# input4.net
KiCad netlist of a schematic drawn in Altium Designer
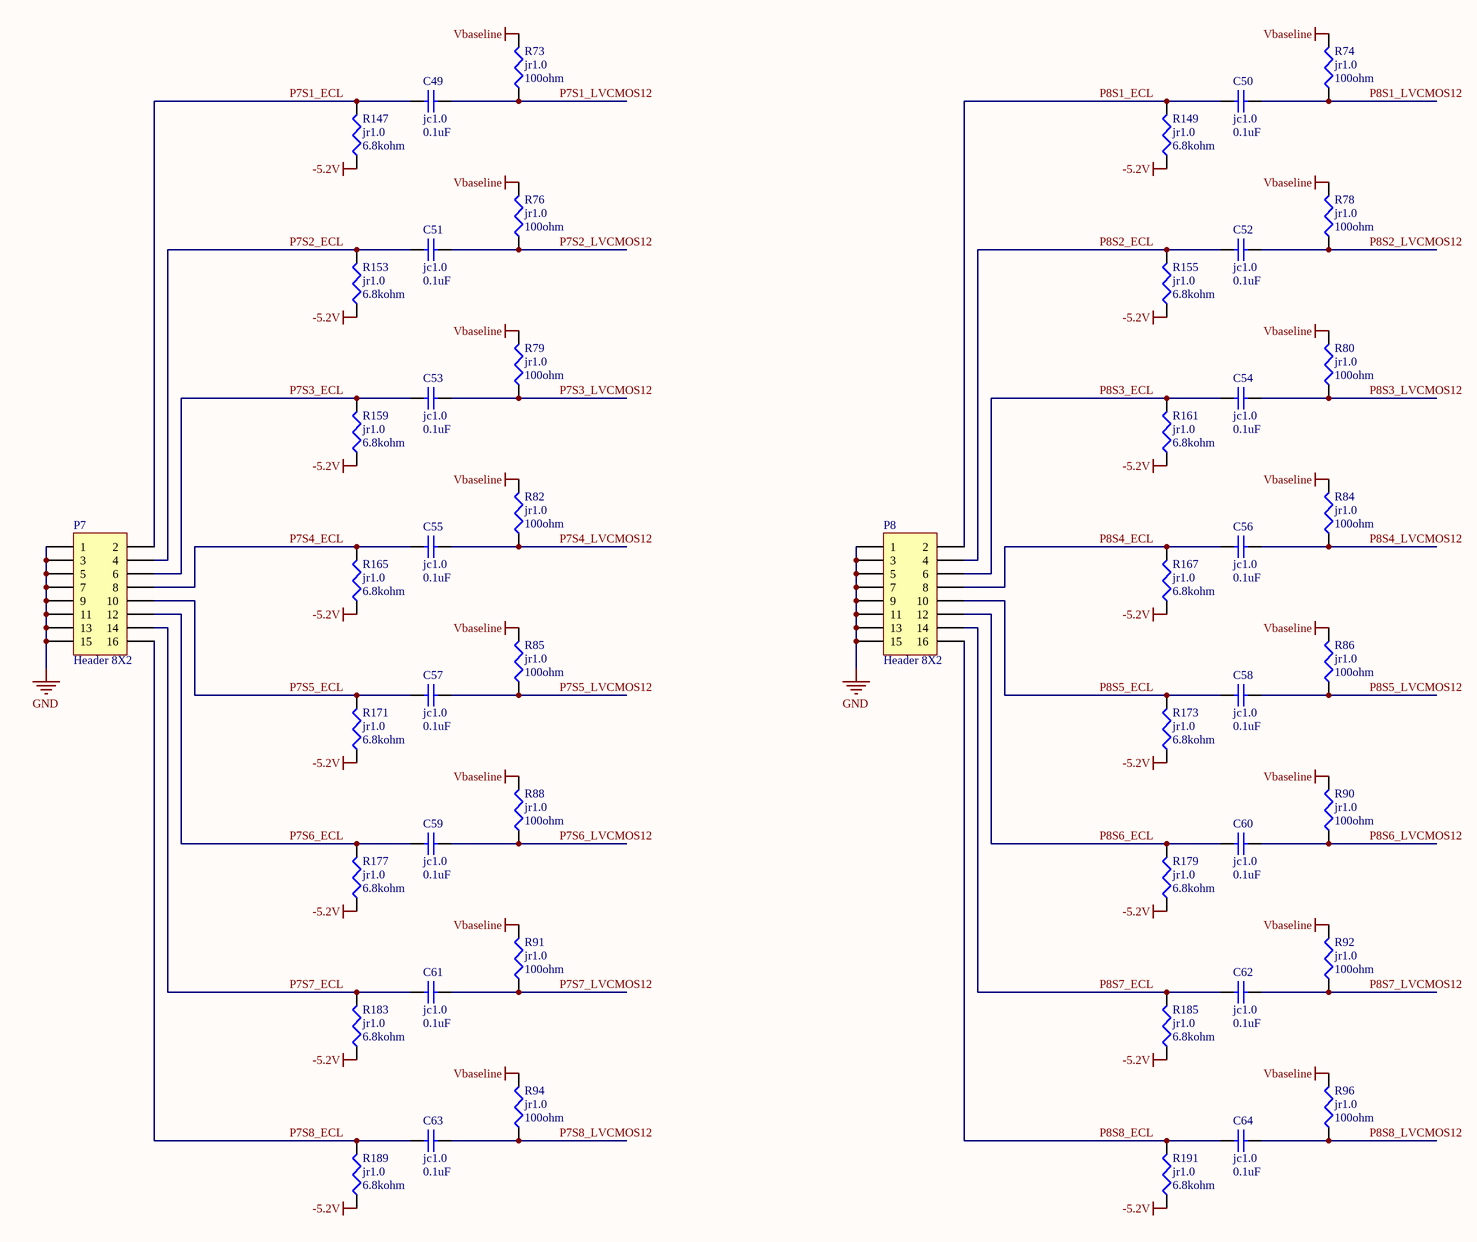
[diagram p0: input4.SchDoc]

(export (version "E")
  (design (tool "Eeschema 10.0.6"))
  (components
    (comp (ref "C49")
      (value "jc1.0")
      (footprint "0402")
      (description "Capacitor")
      (fields (field (name "ALTIUM_VALUE") "0.1uF") (field (name "PUBLISHER") "Altium Limited"))
      (libsource (lib "LIB01DXP2006SchLib") (part "Cap"))
    )
    (comp (ref "C50")
      (value "jc1.0")
      (footprint "0402")
      (description "Capacitor")
      (fields (field (name "ALTIUM_VALUE") "0.1uF") (field (name "PUBLISHER") "Altium Limited"))
      (libsource (lib "LIB01DXP2006SchLib") (part "Cap"))
    )
    (comp (ref "C51")
      (value "jc1.0")
      (footprint "0402")
      (description "Capacitor")
      (fields (field (name "ALTIUM_VALUE") "0.1uF") (field (name "PUBLISHER") "Altium Limited"))
      (libsource (lib "LIB01DXP2006SchLib") (part "Cap"))
    )
    (comp (ref "C52")
      (value "jc1.0")
      (footprint "0402")
      (description "Capacitor")
      (fields (field (name "ALTIUM_VALUE") "0.1uF") (field (name "PUBLISHER") "Altium Limited"))
      (libsource (lib "LIB01DXP2006SchLib") (part "Cap"))
    )
    (comp (ref "C53")
      (value "jc1.0")
      (footprint "0402")
      (description "Capacitor")
      (fields (field (name "ALTIUM_VALUE") "0.1uF") (field (name "PUBLISHER") "Altium Limited"))
      (libsource (lib "LIB01DXP2006SchLib") (part "Cap"))
    )
    (comp (ref "C54")
      (value "jc1.0")
      (footprint "0402")
      (description "Capacitor")
      (fields (field (name "ALTIUM_VALUE") "0.1uF") (field (name "PUBLISHER") "Altium Limited"))
      (libsource (lib "LIB01DXP2006SchLib") (part "Cap"))
    )
    (comp (ref "C55")
      (value "jc1.0")
      (footprint "0402")
      (description "Capacitor")
      (fields (field (name "ALTIUM_VALUE") "0.1uF") (field (name "PUBLISHER") "Altium Limited"))
      (libsource (lib "LIB01DXP2006SchLib") (part "Cap"))
    )
    (comp (ref "C56")
      (value "jc1.0")
      (footprint "0402")
      (description "Capacitor")
      (fields (field (name "ALTIUM_VALUE") "0.1uF") (field (name "PUBLISHER") "Altium Limited"))
      (libsource (lib "LIB01DXP2006SchLib") (part "Cap"))
    )
    (comp (ref "C57")
      (value "jc1.0")
      (footprint "0402")
      (description "Capacitor")
      (fields (field (name "ALTIUM_VALUE") "0.1uF") (field (name "PUBLISHER") "Altium Limited"))
      (libsource (lib "LIB01DXP2006SchLib") (part "Cap"))
    )
    (comp (ref "C58")
      (value "jc1.0")
      (footprint "0402")
      (description "Capacitor")
      (fields (field (name "ALTIUM_VALUE") "0.1uF") (field (name "PUBLISHER") "Altium Limited"))
      (libsource (lib "LIB01DXP2006SchLib") (part "Cap"))
    )
    (comp (ref "C59")
      (value "jc1.0")
      (footprint "0402")
      (description "Capacitor")
      (fields (field (name "ALTIUM_VALUE") "0.1uF") (field (name "PUBLISHER") "Altium Limited"))
      (libsource (lib "LIB01DXP2006SchLib") (part "Cap"))
    )
    (comp (ref "C60")
      (value "jc1.0")
      (footprint "0402")
      (description "Capacitor")
      (fields (field (name "ALTIUM_VALUE") "0.1uF") (field (name "PUBLISHER") "Altium Limited"))
      (libsource (lib "LIB01DXP2006SchLib") (part "Cap"))
    )
    (comp (ref "C61")
      (value "jc1.0")
      (footprint "0402")
      (description "Capacitor")
      (fields (field (name "ALTIUM_VALUE") "0.1uF") (field (name "PUBLISHER") "Altium Limited"))
      (libsource (lib "LIB01DXP2006SchLib") (part "Cap"))
    )
    (comp (ref "C62")
      (value "jc1.0")
      (footprint "0402")
      (description "Capacitor")
      (fields (field (name "ALTIUM_VALUE") "0.1uF") (field (name "PUBLISHER") "Altium Limited"))
      (libsource (lib "LIB01DXP2006SchLib") (part "Cap"))
    )
    (comp (ref "C63")
      (value "jc1.0")
      (footprint "0402")
      (description "Capacitor")
      (fields (field (name "ALTIUM_VALUE") "0.1uF") (field (name "PUBLISHER") "Altium Limited"))
      (libsource (lib "LIB01DXP2006SchLib") (part "Cap"))
    )
    (comp (ref "C64")
      (value "jc1.0")
      (footprint "0402")
      (description "Capacitor")
      (fields (field (name "ALTIUM_VALUE") "0.1uF") (field (name "PUBLISHER") "Altium Limited"))
      (libsource (lib "LIB01DXP2006SchLib") (part "Cap"))
    )
    (comp (ref "P7")
      (value "Header 8X2")
      (footprint "HDR2X8")
      (description "Header, 8-Pin, Dual row")
      (fields (field (name "PUBLISHER") "Altium Limited"))
      (libsource (lib "Miscellaneous Connectors") (part "Header 8X2"))
    )
    (comp (ref "P8")
      (value "Header 8X2")
      (footprint "HDR2X8")
      (description "Header, 8-Pin, Dual row")
      (fields (field (name "PUBLISHER") "Altium Limited"))
      (libsource (lib "Miscellaneous Connectors") (part "Header 8X2"))
    )
    (comp (ref "R73")
      (value "jr1.0")
      (footprint "0402")
      (description "Resistor")
      (fields (field (name "ALTIUM_VALUE") "100ohm") (field (name "PUBLISHER") "Altium Limited"))
      (libsource (lib "LIB01DXP2006SchLib") (part "Res"))
    )
    (comp (ref "R74")
      (value "jr1.0")
      (footprint "0402")
      (description "Resistor")
      (fields (field (name "ALTIUM_VALUE") "100ohm") (field (name "PUBLISHER") "Altium Limited"))
      (libsource (lib "LIB01DXP2006SchLib") (part "Res"))
    )
    (comp (ref "R76")
      (value "jr1.0")
      (footprint "0402")
      (description "Resistor")
      (fields (field (name "ALTIUM_VALUE") "100ohm") (field (name "PUBLISHER") "Altium Limited"))
      (libsource (lib "LIB01DXP2006SchLib") (part "Res"))
    )
    (comp (ref "R78")
      (value "jr1.0")
      (footprint "0402")
      (description "Resistor")
      (fields (field (name "ALTIUM_VALUE") "100ohm") (field (name "PUBLISHER") "Altium Limited"))
      (libsource (lib "LIB01DXP2006SchLib") (part "Res"))
    )
    (comp (ref "R79")
      (value "jr1.0")
      (footprint "0402")
      (description "Resistor")
      (fields (field (name "ALTIUM_VALUE") "100ohm") (field (name "PUBLISHER") "Altium Limited"))
      (libsource (lib "LIB01DXP2006SchLib") (part "Res"))
    )
    (comp (ref "R80")
      (value "jr1.0")
      (footprint "0402")
      (description "Resistor")
      (fields (field (name "ALTIUM_VALUE") "100ohm") (field (name "PUBLISHER") "Altium Limited"))
      (libsource (lib "LIB01DXP2006SchLib") (part "Res"))
    )
    (comp (ref "R82")
      (value "jr1.0")
      (footprint "0402")
      (description "Resistor")
      (fields (field (name "ALTIUM_VALUE") "100ohm") (field (name "PUBLISHER") "Altium Limited"))
      (libsource (lib "LIB01DXP2006SchLib") (part "Res"))
    )
    (comp (ref "R84")
      (value "jr1.0")
      (footprint "0402")
      (description "Resistor")
      (fields (field (name "ALTIUM_VALUE") "100ohm") (field (name "PUBLISHER") "Altium Limited"))
      (libsource (lib "LIB01DXP2006SchLib") (part "Res"))
    )
    (comp (ref "R85")
      (value "jr1.0")
      (footprint "0402")
      (description "Resistor")
      (fields (field (name "ALTIUM_VALUE") "100ohm") (field (name "PUBLISHER") "Altium Limited"))
      (libsource (lib "LIB01DXP2006SchLib") (part "Res"))
    )
    (comp (ref "R86")
      (value "jr1.0")
      (footprint "0402")
      (description "Resistor")
      (fields (field (name "ALTIUM_VALUE") "100ohm") (field (name "PUBLISHER") "Altium Limited"))
      (libsource (lib "LIB01DXP2006SchLib") (part "Res"))
    )
    (comp (ref "R88")
      (value "jr1.0")
      (footprint "0402")
      (description "Resistor")
      (fields (field (name "ALTIUM_VALUE") "100ohm") (field (name "PUBLISHER") "Altium Limited"))
      (libsource (lib "LIB01DXP2006SchLib") (part "Res"))
    )
    (comp (ref "R90")
      (value "jr1.0")
      (footprint "0402")
      (description "Resistor")
      (fields (field (name "ALTIUM_VALUE") "100ohm") (field (name "PUBLISHER") "Altium Limited"))
      (libsource (lib "LIB01DXP2006SchLib") (part "Res"))
    )
    (comp (ref "R91")
      (value "jr1.0")
      (footprint "0402")
      (description "Resistor")
      (fields (field (name "ALTIUM_VALUE") "100ohm") (field (name "PUBLISHER") "Altium Limited"))
      (libsource (lib "LIB01DXP2006SchLib") (part "Res"))
    )
    (comp (ref "R92")
      (value "jr1.0")
      (footprint "0402")
      (description "Resistor")
      (fields (field (name "ALTIUM_VALUE") "100ohm") (field (name "PUBLISHER") "Altium Limited"))
      (libsource (lib "LIB01DXP2006SchLib") (part "Res"))
    )
    (comp (ref "R94")
      (value "jr1.0")
      (footprint "0402")
      (description "Resistor")
      (fields (field (name "ALTIUM_VALUE") "100ohm") (field (name "PUBLISHER") "Altium Limited"))
      (libsource (lib "LIB01DXP2006SchLib") (part "Res"))
    )
    (comp (ref "R96")
      (value "jr1.0")
      (footprint "0402")
      (description "Resistor")
      (fields (field (name "ALTIUM_VALUE") "100ohm") (field (name "PUBLISHER") "Altium Limited"))
      (libsource (lib "LIB01DXP2006SchLib") (part "Res"))
    )
    (comp (ref "R147")
      (value "jr1.0")
      (footprint "0402")
      (description "Resistor")
      (fields (field (name "ALTIUM_VALUE") "6.8kohm") (field (name "PUBLISHER") "Altium Limited"))
      (libsource (lib "LIB01DXP2006SchLib") (part "Res"))
    )
    (comp (ref "R149")
      (value "jr1.0")
      (footprint "0402")
      (description "Resistor")
      (fields (field (name "ALTIUM_VALUE") "6.8kohm") (field (name "PUBLISHER") "Altium Limited"))
      (libsource (lib "LIB01DXP2006SchLib") (part "Res"))
    )
    (comp (ref "R153")
      (value "jr1.0")
      (footprint "0402")
      (description "Resistor")
      (fields (field (name "ALTIUM_VALUE") "6.8kohm") (field (name "PUBLISHER") "Altium Limited"))
      (libsource (lib "LIB01DXP2006SchLib") (part "Res"))
    )
    (comp (ref "R155")
      (value "jr1.0")
      (footprint "0402")
      (description "Resistor")
      (fields (field (name "ALTIUM_VALUE") "6.8kohm") (field (name "PUBLISHER") "Altium Limited"))
      (libsource (lib "LIB01DXP2006SchLib") (part "Res"))
    )
    (comp (ref "R159")
      (value "jr1.0")
      (footprint "0402")
      (description "Resistor")
      (fields (field (name "ALTIUM_VALUE") "6.8kohm") (field (name "PUBLISHER") "Altium Limited"))
      (libsource (lib "LIB01DXP2006SchLib") (part "Res"))
    )
    (comp (ref "R161")
      (value "jr1.0")
      (footprint "0402")
      (description "Resistor")
      (fields (field (name "ALTIUM_VALUE") "6.8kohm") (field (name "PUBLISHER") "Altium Limited"))
      (libsource (lib "LIB01DXP2006SchLib") (part "Res"))
    )
    (comp (ref "R165")
      (value "jr1.0")
      (footprint "0402")
      (description "Resistor")
      (fields (field (name "ALTIUM_VALUE") "6.8kohm") (field (name "PUBLISHER") "Altium Limited"))
      (libsource (lib "LIB01DXP2006SchLib") (part "Res"))
    )
    (comp (ref "R167")
      (value "jr1.0")
      (footprint "0402")
      (description "Resistor")
      (fields (field (name "ALTIUM_VALUE") "6.8kohm") (field (name "PUBLISHER") "Altium Limited"))
      (libsource (lib "LIB01DXP2006SchLib") (part "Res"))
    )
    (comp (ref "R171")
      (value "jr1.0")
      (footprint "0402")
      (description "Resistor")
      (fields (field (name "ALTIUM_VALUE") "6.8kohm") (field (name "PUBLISHER") "Altium Limited"))
      (libsource (lib "LIB01DXP2006SchLib") (part "Res"))
    )
    (comp (ref "R173")
      (value "jr1.0")
      (footprint "0402")
      (description "Resistor")
      (fields (field (name "ALTIUM_VALUE") "6.8kohm") (field (name "PUBLISHER") "Altium Limited"))
      (libsource (lib "LIB01DXP2006SchLib") (part "Res"))
    )
    (comp (ref "R177")
      (value "jr1.0")
      (footprint "0402")
      (description "Resistor")
      (fields (field (name "ALTIUM_VALUE") "6.8kohm") (field (name "PUBLISHER") "Altium Limited"))
      (libsource (lib "LIB01DXP2006SchLib") (part "Res"))
    )
    (comp (ref "R179")
      (value "jr1.0")
      (footprint "0402")
      (description "Resistor")
      (fields (field (name "ALTIUM_VALUE") "6.8kohm") (field (name "PUBLISHER") "Altium Limited"))
      (libsource (lib "LIB01DXP2006SchLib") (part "Res"))
    )
    (comp (ref "R183")
      (value "jr1.0")
      (footprint "0402")
      (description "Resistor")
      (fields (field (name "ALTIUM_VALUE") "6.8kohm") (field (name "PUBLISHER") "Altium Limited"))
      (libsource (lib "LIB01DXP2006SchLib") (part "Res"))
    )
    (comp (ref "R185")
      (value "jr1.0")
      (footprint "0402")
      (description "Resistor")
      (fields (field (name "ALTIUM_VALUE") "6.8kohm") (field (name "PUBLISHER") "Altium Limited"))
      (libsource (lib "LIB01DXP2006SchLib") (part "Res"))
    )
    (comp (ref "R189")
      (value "jr1.0")
      (footprint "0402")
      (description "Resistor")
      (fields (field (name "ALTIUM_VALUE") "6.8kohm") (field (name "PUBLISHER") "Altium Limited"))
      (libsource (lib "LIB01DXP2006SchLib") (part "Res"))
    )
    (comp (ref "R191")
      (value "jr1.0")
      (footprint "0402")
      (description "Resistor")
      (fields (field (name "ALTIUM_VALUE") "6.8kohm") (field (name "PUBLISHER") "Altium Limited"))
      (libsource (lib "LIB01DXP2006SchLib") (part "Res"))
    )
  )
  (nets
    (net (code "1") (name "-5.2V") (class "Default")
      (node (ref "R147") (pin "1") (pinfunction "1_1") (pintype "passive"))
      (node (ref "R149") (pin "1") (pinfunction "1_1") (pintype "passive"))
      (node (ref "R153") (pin "1") (pinfunction "1_1") (pintype "passive"))
      (node (ref "R155") (pin "1") (pinfunction "1_1") (pintype "passive"))
      (node (ref "R159") (pin "1") (pinfunction "1_1") (pintype "passive"))
      (node (ref "R161") (pin "1") (pinfunction "1_1") (pintype "passive"))
      (node (ref "R165") (pin "1") (pinfunction "1_1") (pintype "passive"))
      (node (ref "R167") (pin "1") (pinfunction "1_1") (pintype "passive"))
      (node (ref "R171") (pin "1") (pinfunction "1_1") (pintype "passive"))
      (node (ref "R173") (pin "1") (pinfunction "1_1") (pintype "passive"))
      (node (ref "R177") (pin "1") (pinfunction "1_1") (pintype "passive"))
      (node (ref "R179") (pin "1") (pinfunction "1_1") (pintype "passive"))
      (node (ref "R183") (pin "1") (pinfunction "1_1") (pintype "passive"))
      (node (ref "R185") (pin "1") (pinfunction "1_1") (pintype "passive"))
      (node (ref "R189") (pin "1") (pinfunction "1_1") (pintype "passive"))
      (node (ref "R191") (pin "1") (pinfunction "1_1") (pintype "passive"))
    )
    (net (code "2") (name "/P7S1_ECL") (class "Default")
      (node (ref "C49") (pin "1") (pinfunction "1_1") (pintype "passive"))
      (node (ref "P7") (pin "2") (pinfunction "2_2") (pintype "passive"))
      (node (ref "R147") (pin "2") (pinfunction "2_2") (pintype "passive"))
    )
    (net (code "3") (name "/P7S1_LVCMOS12") (class "Default")
      (node (ref "C49") (pin "2") (pinfunction "2_2") (pintype "passive"))
      (node (ref "R73") (pin "1") (pinfunction "1_1") (pintype "passive"))
    )
    (net (code "4") (name "/P7S2_ECL") (class "Default")
      (node (ref "C51") (pin "1") (pinfunction "1_1") (pintype "passive"))
      (node (ref "P7") (pin "4") (pinfunction "4_4") (pintype "passive"))
      (node (ref "R153") (pin "2") (pinfunction "2_2") (pintype "passive"))
    )
    (net (code "5") (name "/P7S2_LVCMOS12") (class "Default")
      (node (ref "C51") (pin "2") (pinfunction "2_2") (pintype "passive"))
      (node (ref "R76") (pin "1") (pinfunction "1_1") (pintype "passive"))
    )
    (net (code "6") (name "/P7S3_ECL") (class "Default")
      (node (ref "C53") (pin "1") (pinfunction "1_1") (pintype "passive"))
      (node (ref "P7") (pin "6") (pinfunction "6_6") (pintype "passive"))
      (node (ref "R159") (pin "2") (pinfunction "2_2") (pintype "passive"))
    )
    (net (code "7") (name "/P7S3_LVCMOS12") (class "Default")
      (node (ref "C53") (pin "2") (pinfunction "2_2") (pintype "passive"))
      (node (ref "R79") (pin "1") (pinfunction "1_1") (pintype "passive"))
    )
    (net (code "8") (name "/P7S4_ECL") (class "Default")
      (node (ref "C55") (pin "1") (pinfunction "1_1") (pintype "passive"))
      (node (ref "P7") (pin "8") (pinfunction "8_8") (pintype "passive"))
      (node (ref "R165") (pin "2") (pinfunction "2_2") (pintype "passive"))
    )
    (net (code "9") (name "/P7S4_LVCMOS12") (class "Default")
      (node (ref "C55") (pin "2") (pinfunction "2_2") (pintype "passive"))
      (node (ref "R82") (pin "1") (pinfunction "1_1") (pintype "passive"))
    )
    (net (code "10") (name "/P7S5_ECL") (class "Default")
      (node (ref "C57") (pin "1") (pinfunction "1_1") (pintype "passive"))
      (node (ref "P7") (pin "10") (pinfunction "10_10") (pintype "passive"))
      (node (ref "R171") (pin "2") (pinfunction "2_2") (pintype "passive"))
    )
    (net (code "11") (name "/P7S5_LVCMOS12") (class "Default")
      (node (ref "C57") (pin "2") (pinfunction "2_2") (pintype "passive"))
      (node (ref "R85") (pin "1") (pinfunction "1_1") (pintype "passive"))
    )
    (net (code "12") (name "/P7S6_ECL") (class "Default")
      (node (ref "C59") (pin "1") (pinfunction "1_1") (pintype "passive"))
      (node (ref "P7") (pin "12") (pinfunction "12_12") (pintype "passive"))
      (node (ref "R177") (pin "2") (pinfunction "2_2") (pintype "passive"))
    )
    (net (code "13") (name "/P7S6_LVCMOS12") (class "Default")
      (node (ref "C59") (pin "2") (pinfunction "2_2") (pintype "passive"))
      (node (ref "R88") (pin "1") (pinfunction "1_1") (pintype "passive"))
    )
    (net (code "14") (name "/P7S7_ECL") (class "Default")
      (node (ref "C61") (pin "1") (pinfunction "1_1") (pintype "passive"))
      (node (ref "P7") (pin "14") (pinfunction "14_14") (pintype "passive"))
      (node (ref "R183") (pin "2") (pinfunction "2_2") (pintype "passive"))
    )
    (net (code "15") (name "/P7S7_LVCMOS12") (class "Default")
      (node (ref "C61") (pin "2") (pinfunction "2_2") (pintype "passive"))
      (node (ref "R91") (pin "1") (pinfunction "1_1") (pintype "passive"))
    )
    (net (code "16") (name "/P7S8_ECL") (class "Default")
      (node (ref "C63") (pin "1") (pinfunction "1_1") (pintype "passive"))
      (node (ref "P7") (pin "16") (pinfunction "16_16") (pintype "passive"))
      (node (ref "R189") (pin "2") (pinfunction "2_2") (pintype "passive"))
    )
    (net (code "17") (name "/P7S8_LVCMOS12") (class "Default")
      (node (ref "C63") (pin "2") (pinfunction "2_2") (pintype "passive"))
      (node (ref "R94") (pin "1") (pinfunction "1_1") (pintype "passive"))
    )
    (net (code "18") (name "/P8S1_ECL") (class "Default")
      (node (ref "C50") (pin "1") (pinfunction "1_1") (pintype "passive"))
      (node (ref "P8") (pin "2") (pinfunction "2_2") (pintype "passive"))
      (node (ref "R149") (pin "2") (pinfunction "2_2") (pintype "passive"))
    )
    (net (code "19") (name "/P8S1_LVCMOS12") (class "Default")
      (node (ref "C50") (pin "2") (pinfunction "2_2") (pintype "passive"))
      (node (ref "R74") (pin "1") (pinfunction "1_1") (pintype "passive"))
    )
    (net (code "20") (name "/P8S2_ECL") (class "Default")
      (node (ref "C52") (pin "1") (pinfunction "1_1") (pintype "passive"))
      (node (ref "P8") (pin "4") (pinfunction "4_4") (pintype "passive"))
      (node (ref "R155") (pin "2") (pinfunction "2_2") (pintype "passive"))
    )
    (net (code "21") (name "/P8S2_LVCMOS12") (class "Default")
      (node (ref "C52") (pin "2") (pinfunction "2_2") (pintype "passive"))
      (node (ref "R78") (pin "1") (pinfunction "1_1") (pintype "passive"))
    )
    (net (code "22") (name "/P8S3_ECL") (class "Default")
      (node (ref "C54") (pin "1") (pinfunction "1_1") (pintype "passive"))
      (node (ref "P8") (pin "6") (pinfunction "6_6") (pintype "passive"))
      (node (ref "R161") (pin "2") (pinfunction "2_2") (pintype "passive"))
    )
    (net (code "23") (name "/P8S3_LVCMOS12") (class "Default")
      (node (ref "C54") (pin "2") (pinfunction "2_2") (pintype "passive"))
      (node (ref "R80") (pin "1") (pinfunction "1_1") (pintype "passive"))
    )
    (net (code "24") (name "/P8S4_ECL") (class "Default")
      (node (ref "C56") (pin "1") (pinfunction "1_1") (pintype "passive"))
      (node (ref "P8") (pin "8") (pinfunction "8_8") (pintype "passive"))
      (node (ref "R167") (pin "2") (pinfunction "2_2") (pintype "passive"))
    )
    (net (code "25") (name "/P8S4_LVCMOS12") (class "Default")
      (node (ref "C56") (pin "2") (pinfunction "2_2") (pintype "passive"))
      (node (ref "R84") (pin "1") (pinfunction "1_1") (pintype "passive"))
    )
    (net (code "26") (name "/P8S5_ECL") (class "Default")
      (node (ref "C58") (pin "1") (pinfunction "1_1") (pintype "passive"))
      (node (ref "P8") (pin "10") (pinfunction "10_10") (pintype "passive"))
      (node (ref "R173") (pin "2") (pinfunction "2_2") (pintype "passive"))
    )
    (net (code "27") (name "/P8S5_LVCMOS12") (class "Default")
      (node (ref "C58") (pin "2") (pinfunction "2_2") (pintype "passive"))
      (node (ref "R86") (pin "1") (pinfunction "1_1") (pintype "passive"))
    )
    (net (code "28") (name "/P8S6_ECL") (class "Default")
      (node (ref "C60") (pin "1") (pinfunction "1_1") (pintype "passive"))
      (node (ref "P8") (pin "12") (pinfunction "12_12") (pintype "passive"))
      (node (ref "R179") (pin "2") (pinfunction "2_2") (pintype "passive"))
    )
    (net (code "29") (name "/P8S6_LVCMOS12") (class "Default")
      (node (ref "C60") (pin "2") (pinfunction "2_2") (pintype "passive"))
      (node (ref "R90") (pin "1") (pinfunction "1_1") (pintype "passive"))
    )
    (net (code "30") (name "/P8S7_ECL") (class "Default")
      (node (ref "C62") (pin "1") (pinfunction "1_1") (pintype "passive"))
      (node (ref "P8") (pin "14") (pinfunction "14_14") (pintype "passive"))
      (node (ref "R185") (pin "2") (pinfunction "2_2") (pintype "passive"))
    )
    (net (code "31") (name "/P8S7_LVCMOS12") (class "Default")
      (node (ref "C62") (pin "2") (pinfunction "2_2") (pintype "passive"))
      (node (ref "R92") (pin "1") (pinfunction "1_1") (pintype "passive"))
    )
    (net (code "32") (name "/P8S8_ECL") (class "Default")
      (node (ref "C64") (pin "1") (pinfunction "1_1") (pintype "passive"))
      (node (ref "P8") (pin "16") (pinfunction "16_16") (pintype "passive"))
      (node (ref "R191") (pin "2") (pinfunction "2_2") (pintype "passive"))
    )
    (net (code "33") (name "/P8S8_LVCMOS12") (class "Default")
      (node (ref "C64") (pin "2") (pinfunction "2_2") (pintype "passive"))
      (node (ref "R96") (pin "1") (pinfunction "1_1") (pintype "passive"))
    )
    (net (code "34") (name "GND") (class "Default")
      (node (ref "P7") (pin "1") (pinfunction "1_1") (pintype "passive"))
      (node (ref "P7") (pin "11") (pinfunction "11_11") (pintype "passive"))
      (node (ref "P7") (pin "13") (pinfunction "13_13") (pintype "passive"))
      (node (ref "P7") (pin "15") (pinfunction "15_15") (pintype "passive"))
      (node (ref "P7") (pin "3") (pinfunction "3_3") (pintype "passive"))
      (node (ref "P7") (pin "5") (pinfunction "5_5") (pintype "passive"))
      (node (ref "P7") (pin "7") (pinfunction "7_7") (pintype "passive"))
      (node (ref "P7") (pin "9") (pinfunction "9_9") (pintype "passive"))
      (node (ref "P8") (pin "1") (pinfunction "1_1") (pintype "passive"))
      (node (ref "P8") (pin "11") (pinfunction "11_11") (pintype "passive"))
      (node (ref "P8") (pin "13") (pinfunction "13_13") (pintype "passive"))
      (node (ref "P8") (pin "15") (pinfunction "15_15") (pintype "passive"))
      (node (ref "P8") (pin "3") (pinfunction "3_3") (pintype "passive"))
      (node (ref "P8") (pin "5") (pinfunction "5_5") (pintype "passive"))
      (node (ref "P8") (pin "7") (pinfunction "7_7") (pintype "passive"))
      (node (ref "P8") (pin "9") (pinfunction "9_9") (pintype "passive"))
    )
    (net (code "35") (name "Vbaseline") (class "Default")
      (node (ref "R73") (pin "2") (pinfunction "2_2") (pintype "passive"))
      (node (ref "R74") (pin "2") (pinfunction "2_2") (pintype "passive"))
      (node (ref "R76") (pin "2") (pinfunction "2_2") (pintype "passive"))
      (node (ref "R78") (pin "2") (pinfunction "2_2") (pintype "passive"))
      (node (ref "R79") (pin "2") (pinfunction "2_2") (pintype "passive"))
      (node (ref "R80") (pin "2") (pinfunction "2_2") (pintype "passive"))
      (node (ref "R82") (pin "2") (pinfunction "2_2") (pintype "passive"))
      (node (ref "R84") (pin "2") (pinfunction "2_2") (pintype "passive"))
      (node (ref "R85") (pin "2") (pinfunction "2_2") (pintype "passive"))
      (node (ref "R86") (pin "2") (pinfunction "2_2") (pintype "passive"))
      (node (ref "R88") (pin "2") (pinfunction "2_2") (pintype "passive"))
      (node (ref "R90") (pin "2") (pinfunction "2_2") (pintype "passive"))
      (node (ref "R91") (pin "2") (pinfunction "2_2") (pintype "passive"))
      (node (ref "R92") (pin "2") (pinfunction "2_2") (pintype "passive"))
      (node (ref "R94") (pin "2") (pinfunction "2_2") (pintype "passive"))
      (node (ref "R96") (pin "2") (pinfunction "2_2") (pintype "passive"))
    )
  )
)
